# SparkFun_NanoBeacon_Lite_Board_-_IN100.net
KiCad netlist of a schematic drawn in EAGLE
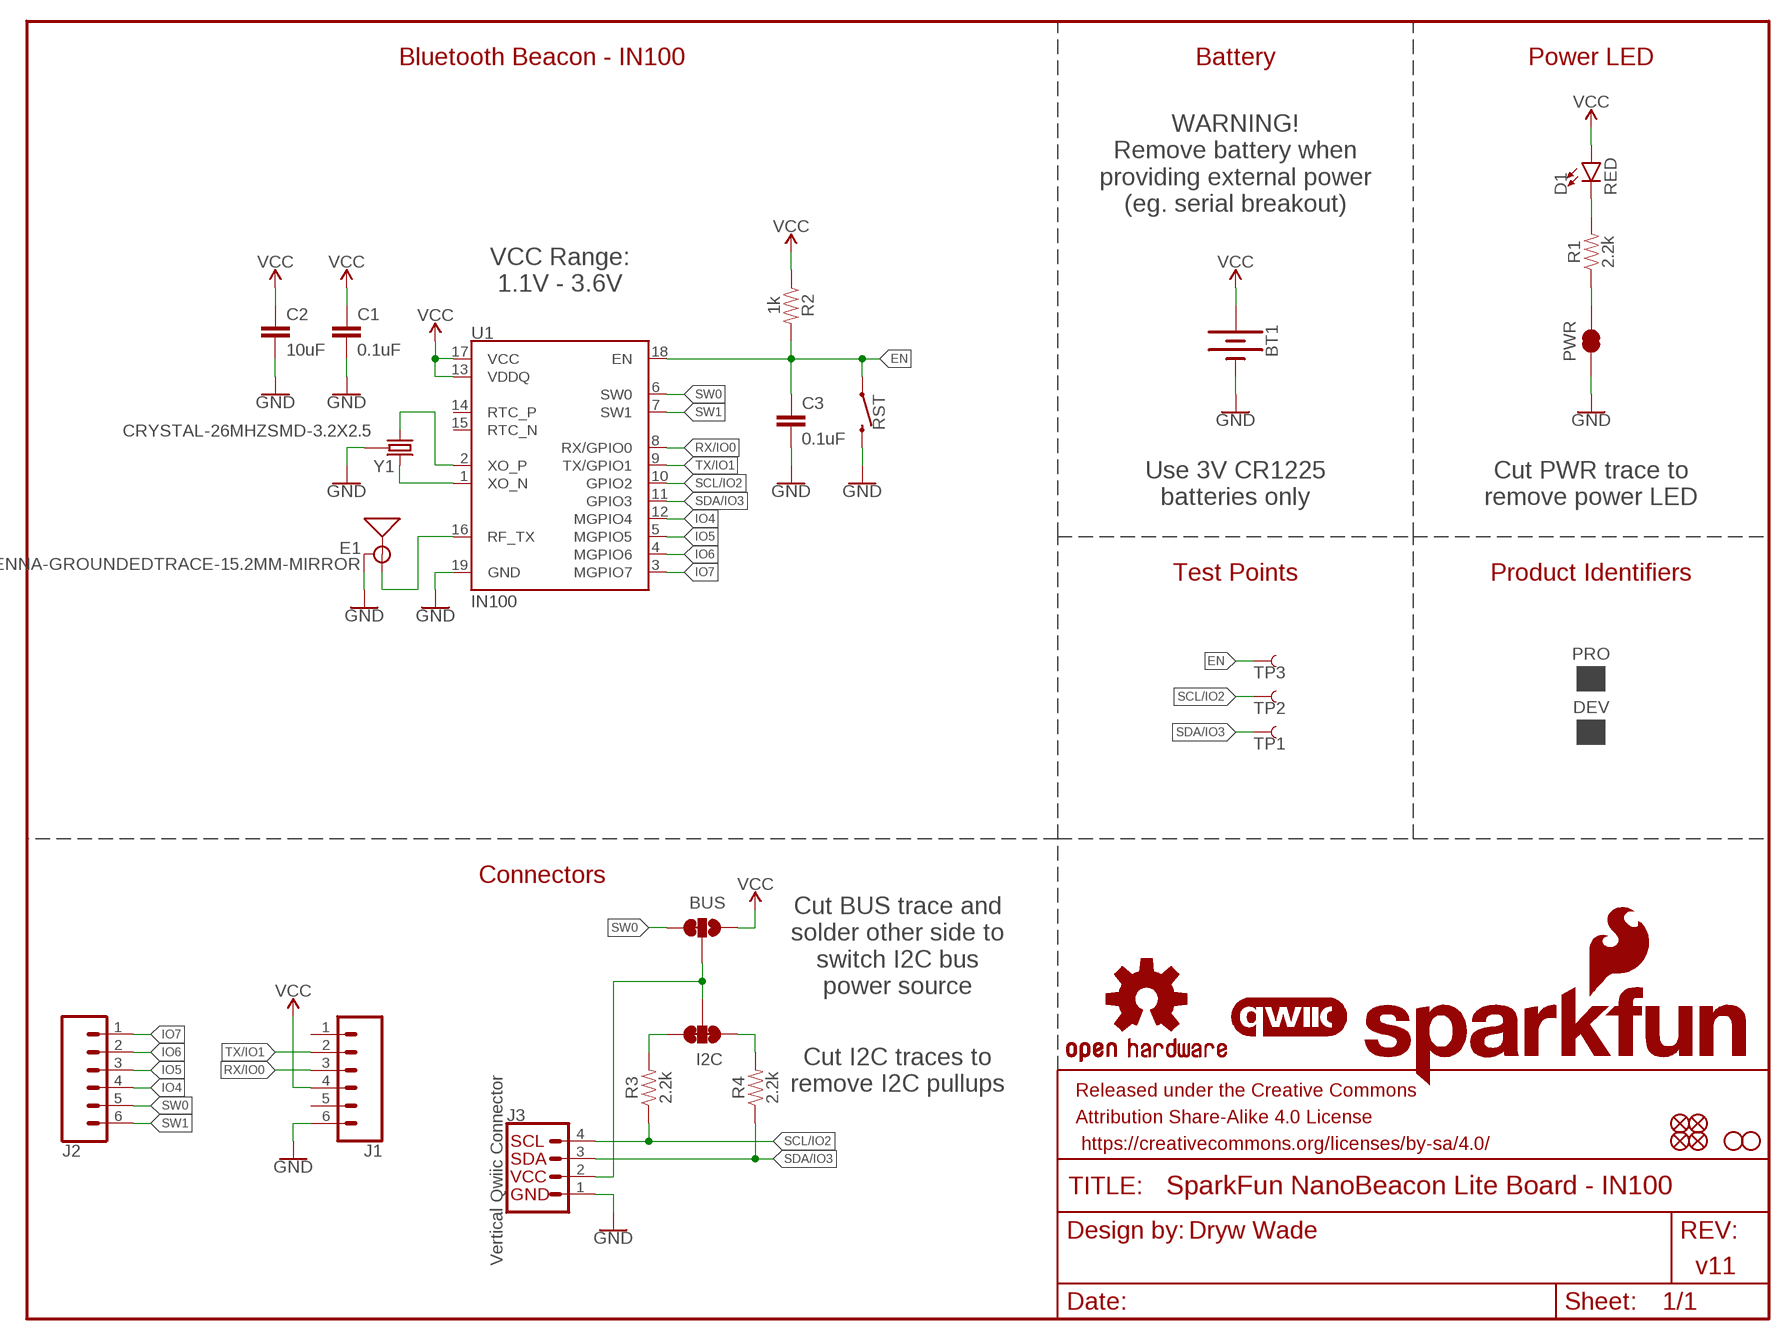
[diagram p0: schematic, sheet 1]

(export (version "E")
  (design (tool "Eeschema 10.0.6"))
  (components
    (comp (ref "BT1")
      (value "BATTERY-12MM_SMD_BOTH_PWR_PADS")
      (footprint "eagle-import:BATTCON_12MM")
      (libsource (lib "eagle-import") (part "BATTERY-12MM_SMD_BOTH_PWR_PADS"))
    )
    (comp (ref "BUS")
      (value "JUMPER-SMT_3_1-NC_TRACE_SILK")
      (footprint "eagle-import:SMT-JUMPER_3_1-NC_TRACE_SILK")
      (libsource (lib "eagle-import") (part "JUMPER-SMT_3_1-NC_TRACE_SILK"))
    )
    (comp (ref "C1")
      (value "0.1uF")
      (footprint "eagle-import:0402-TIGHT")
      (libsource (lib "eagle-import") (part "0.1UF-0402T-6.3V-10%-X7R"))
    )
    (comp (ref "C2")
      (value "10uF")
      (footprint "eagle-import:0402-TIGHT")
      (libsource (lib "eagle-import") (part "10UF-0402T-6.3V-20%"))
    )
    (comp (ref "C3")
      (value "0.1uF")
      (footprint "eagle-import:0402-TIGHT")
      (libsource (lib "eagle-import") (part "0.1UF-0402T-6.3V-10%-X7R"))
    )
    (comp (ref "D1")
      (value "RED")
      (footprint "eagle-import:LED-0402")
      (libsource (lib "eagle-import") (part "LED-RED_0402"))
    )
    (comp (ref "DEV")
      (value "PROD_ID_PASTE_SILK")
      (footprint "eagle-import:PRODUCT_IDENT_PASTE_SILK")
      (libsource (lib "eagle-import") (part "PROD_ID_PASTE_SILK"))
    )
    (comp (ref "E1")
      (value "ANTENNA-GROUNDEDTRACE-15.2MM-MIRROR")
      (footprint "eagle-import:TRACE_ANTENNA_2.4GHZ_15.2MM_MIRROR")
      (libsource (lib "eagle-import") (part "ANTENNA-GROUNDEDTRACE-15.2MM-MIRROR"))
    )
    (comp (ref "FD1")
      (value "FIDUCIAL1X2")
      (footprint "eagle-import:FIDUCIAL-1X2")
      (libsource (lib "eagle-import") (part "FIDUCIAL1X2"))
    )
    (comp (ref "FD2")
      (value "FIDUCIAL1X2")
      (footprint "eagle-import:FIDUCIAL-1X2")
      (libsource (lib "eagle-import") (part "FIDUCIAL1X2"))
    )
    (comp (ref "FD3")
      (value "FIDUCIAL1X2")
      (footprint "eagle-import:FIDUCIAL-1X2")
      (libsource (lib "eagle-import") (part "FIDUCIAL1X2"))
    )
    (comp (ref "FD4")
      (value "FIDUCIAL1X2")
      (footprint "eagle-import:FIDUCIAL-1X2")
      (libsource (lib "eagle-import") (part "FIDUCIAL1X2"))
    )
    (comp (ref "FRAME1")
      (value "FRAME-LETTER")
      (footprint "eagle-import:CREATIVE_COMMONS")
      (libsource (lib "eagle-import") (part "FRAME-LETTER"))
    )
    (comp (ref "H1")
      (value "STAND-OFF")
      (footprint "eagle-import:STAND-OFF")
      (libsource (lib "eagle-import") (part "STAND-OFF"))
    )
    (comp (ref "H2")
      (value "STAND-OFF")
      (footprint "eagle-import:STAND-OFF")
      (libsource (lib "eagle-import") (part "STAND-OFF"))
    )
    (comp (ref "I2C")
      (value "JUMPER-SMT_3_2-NC_TRACE_SILK")
      (footprint "eagle-import:SMT-JUMPER_3_2-NC_TRACE_SILK")
      (libsource (lib "eagle-import") (part "JUMPER-SMT_3_2-NC_TRACE_SILK"))
    )
    (comp (ref "J1")
      (value "CONN_06NO_SILK_NO_POP")
      (footprint "eagle-import:1X06_NO_SILK")
      (libsource (lib "eagle-import") (part "CONN_06NO_SILK_NO_POP"))
    )
    (comp (ref "J2")
      (value "CONN_06NO_SILK_NO_POP")
      (footprint "eagle-import:1X06_NO_SILK")
      (libsource (lib "eagle-import") (part "CONN_06NO_SILK_NO_POP"))
    )
    (comp (ref "J3")
      (value "Vertical Qwiic Connector")
      (footprint "eagle-import:JST04_1MM_VERT")
      (libsource (lib "eagle-import") (part "QWIIC_CONNECTOR"))
    )
    (comp (ref "LOGO1")
      (value "OSHW-LOGOS")
      (footprint "eagle-import:OSHW-LOGO-S")
      (libsource (lib "eagle-import") (part "OSHW-LOGOS"))
    )
    (comp (ref "LOGO2")
      (value "SFE_LOGO_NAME_FLAME.1_INCH")
      (footprint "eagle-import:SFE_LOGO_NAME_FLAME_.1")
      (libsource (lib "eagle-import") (part "SFE_LOGO_NAME_FLAME.1_INCH"))
    )
    (comp (ref "LOGO3")
      (value "QWIIC_LOGO_5MM")
      (footprint "eagle-import:QWIIC_5MM")
      (libsource (lib "eagle-import") (part "QWIIC_LOGO_5MM"))
    )
    (comp (ref "PRO")
      (value "PROD_ID_PASTE_SILK")
      (footprint "eagle-import:PRODUCT_IDENT_PASTE_SILK")
      (libsource (lib "eagle-import") (part "PROD_ID_PASTE_SILK"))
    )
    (comp (ref "PWR")
      (value "JUMPER-SMT_2_NC_TRACE_SILK")
      (footprint "eagle-import:SMT-JUMPER_2_NC_TRACE_SILK")
      (libsource (lib "eagle-import") (part "JUMPER-SMT_2_NC_TRACE_SILK"))
    )
    (comp (ref "R1")
      (value "2.2k")
      (footprint "eagle-import:0402-TIGHT")
      (libsource (lib "eagle-import") (part "2.2KOHM-0402T-1/16W-1%"))
    )
    (comp (ref "R2")
      (value "1k")
      (footprint "eagle-import:0402-TIGHT")
      (libsource (lib "eagle-import") (part "1KOHM-0402T-1/16W-1%"))
    )
    (comp (ref "R3")
      (value "2.2k")
      (footprint "eagle-import:0402-TIGHT")
      (libsource (lib "eagle-import") (part "2.2KOHM-0402T-1/16W-1%"))
    )
    (comp (ref "R4")
      (value "2.2k")
      (footprint "eagle-import:0402-TIGHT")
      (libsource (lib "eagle-import") (part "2.2KOHM-0402T-1/16W-1%"))
    )
    (comp (ref "RST")
      (value "MOMENTARY-SWITCH-SPST-SMD-4.6X2.8MM")
      (footprint "eagle-import:TACTILE_SWITCH_SMD_4.6X2.8MM")
      (libsource (lib "eagle-import") (part "MOMENTARY-SWITCH-SPST-SMD-4.6X2.8MM"))
    )
    (comp (ref "TP1")
      (value "TEST-POINT3")
      (footprint "eagle-import:PAD.03X.03")
      (libsource (lib "eagle-import") (part "TEST-POINT3"))
    )
    (comp (ref "TP2")
      (value "TEST-POINT3")
      (footprint "eagle-import:PAD.03X.03")
      (libsource (lib "eagle-import") (part "TEST-POINT3"))
    )
    (comp (ref "TP3")
      (value "TEST-POINT3")
      (footprint "eagle-import:PAD.03X.03")
      (libsource (lib "eagle-import") (part "TEST-POINT3"))
    )
    (comp (ref "U1")
      (value "IN100")
      (footprint "eagle-import:IN100")
      (libsource (lib "eagle-import") (part "IN100"))
    )
    (comp (ref "Y1")
      (value "CRYSTAL-26MHZSMD-3.2X2.5")
      (footprint "eagle-import:CRYSTAL-SMD-3.2X2.5MM")
      (libsource (lib "eagle-import") (part "CRYSTAL-26MHZSMD-3.2X2.5"))
    )
  )
  (nets
    (net (code "1") (name "EN") (class "Default")
      (node (ref "C3") (pin "1") (pinfunction "1_1") (pintype "passive"))
      (node (ref "R2") (pin "2") (pinfunction "2_2") (pintype "passive"))
      (node (ref "RST") (pin "1") (pinfunction "1_1") (pintype "passive"))
      (node (ref "RST") (pin "2") (pinfunction "1_2") (pintype "passive"))
      (node (ref "TP3") (pin "1") (pinfunction "1_1") (pintype "bidirectional"))
      (node (ref "U1") (pin "18") (pinfunction "EN_18") (pintype "input"))
    )
    (net (code "2") (name "GND") (class "Default")
      (node (ref "BT1") (pin "GND") (pinfunction "-_GND") (pintype "power_in"))
      (node (ref "C1") (pin "2") (pinfunction "2_2") (pintype "passive"))
      (node (ref "C2") (pin "2") (pinfunction "2_2") (pintype "passive"))
      (node (ref "C3") (pin "2") (pinfunction "2_2") (pintype "passive"))
      (node (ref "E1") (pin "GND") (pinfunction "GND_GND") (pintype "bidirectional"))
      (node (ref "J1") (pin "6") (pinfunction "6_6") (pintype "passive"))
      (node (ref "J3") (pin "1") (pinfunction "1_1") (pintype "power_in"))
      (node (ref "PWR") (pin "1") (pinfunction "1_1") (pintype "passive"))
      (node (ref "RST") (pin "3") (pinfunction "2_3") (pintype "passive"))
      (node (ref "RST") (pin "4") (pinfunction "2_4") (pintype "passive"))
      (node (ref "U1") (pin "19") (pinfunction "GND_19") (pintype "power_in"))
      (node (ref "Y1") (pin "2") (pinfunction "GND_2") (pintype "power_in"))
      (node (ref "Y1") (pin "4") (pinfunction "GND_4") (pintype "power_in"))
    )
    (net (code "3") (name "IO4") (class "Default")
      (node (ref "J2") (pin "4") (pinfunction "4_4") (pintype "passive"))
      (node (ref "U1") (pin "12") (pinfunction "MGPIO4_12") (pintype "bidirectional"))
    )
    (net (code "4") (name "IO5") (class "Default")
      (node (ref "J2") (pin "3") (pinfunction "3_3") (pintype "passive"))
      (node (ref "U1") (pin "5") (pinfunction "MGPIO5_5") (pintype "bidirectional"))
    )
    (net (code "5") (name "IO6") (class "Default")
      (node (ref "J2") (pin "2") (pinfunction "2_2") (pintype "passive"))
      (node (ref "U1") (pin "4") (pinfunction "MGPIO6_4") (pintype "bidirectional"))
    )
    (net (code "6") (name "IO7") (class "Default")
      (node (ref "J2") (pin "1") (pinfunction "1_1") (pintype "passive"))
      (node (ref "U1") (pin "3") (pinfunction "MGPIO7_3") (pintype "bidirectional"))
    )
    (net (code "7") (name "Net-(BUS-Pad2)") (class "Default")
      (node (ref "BUS") (pin "2") (pinfunction "2_2") (pintype "passive"))
      (node (ref "I2C") (pin "2") (pinfunction "2_2") (pintype "passive"))
      (node (ref "J3") (pin "2") (pinfunction "2_2") (pintype "power_in"))
    )
    (net (code "8") (name "Net-(D1-PadC)") (class "Default")
      (node (ref "D1") (pin "C") (pinfunction "C_C") (pintype "passive"))
      (node (ref "R1") (pin "2") (pinfunction "2_2") (pintype "passive"))
    )
    (net (code "9") (name "Net-(E1-SIGNAL)") (class "Default")
      (node (ref "E1") (pin "ANT") (pinfunction "SIGNAL_ANT") (pintype "bidirectional"))
      (node (ref "U1") (pin "16") (pinfunction "RF_TX_16") (pintype "bidirectional"))
    )
    (net (code "10") (name "Net-(I2C-Pad1)") (class "Default")
      (node (ref "I2C") (pin "1") (pinfunction "1_1") (pintype "passive"))
      (node (ref "R4") (pin "2") (pinfunction "2_2") (pintype "passive"))
    )
    (net (code "11") (name "Net-(I2C-Pad3)") (class "Default")
      (node (ref "I2C") (pin "3") (pinfunction "3_3") (pintype "passive"))
      (node (ref "R3") (pin "2") (pinfunction "2_2") (pintype "passive"))
    )
    (net (code "12") (name "Net-(PWR-Pad2)") (class "Default")
      (node (ref "PWR") (pin "2") (pinfunction "2_2") (pintype "passive"))
      (node (ref "R1") (pin "1") (pinfunction "1_1") (pintype "passive"))
    )
    (net (code "13") (name "Net-(U1-XO_N)") (class "Default")
      (node (ref "U1") (pin "1") (pinfunction "XO_N_1") (pintype "bidirectional"))
      (node (ref "Y1") (pin "3") (pinfunction "2_3") (pintype "passive"))
    )
    (net (code "14") (name "Net-(U1-XO_P)") (class "Default")
      (node (ref "U1") (pin "2") (pinfunction "XO_P_2") (pintype "bidirectional"))
      (node (ref "Y1") (pin "1") (pinfunction "1_1") (pintype "passive"))
    )
    (net (code "15") (name "RX{slash}IO0") (class "Default")
      (node (ref "J1") (pin "3") (pinfunction "3_3") (pintype "passive"))
      (node (ref "U1") (pin "8") (pinfunction "RX/GPIO0_8") (pintype "bidirectional"))
    )
    (net (code "16") (name "SCL{slash}IO2") (class "Default")
      (node (ref "J3") (pin "4") (pinfunction "4_4") (pintype "passive"))
      (node (ref "R3") (pin "1") (pinfunction "1_1") (pintype "passive"))
      (node (ref "TP2") (pin "1") (pinfunction "1_1") (pintype "bidirectional"))
      (node (ref "U1") (pin "10") (pinfunction "GPIO2_10") (pintype "bidirectional"))
    )
    (net (code "17") (name "SDA{slash}IO3") (class "Default")
      (node (ref "J3") (pin "3") (pinfunction "3_3") (pintype "passive"))
      (node (ref "R4") (pin "1") (pinfunction "1_1") (pintype "passive"))
      (node (ref "TP1") (pin "1") (pinfunction "1_1") (pintype "bidirectional"))
      (node (ref "U1") (pin "11") (pinfunction "GPIO3_11") (pintype "bidirectional"))
    )
    (net (code "18") (name "SW0") (class "Default")
      (node (ref "BUS") (pin "3") (pinfunction "3_3") (pintype "passive"))
      (node (ref "J2") (pin "5") (pinfunction "5_5") (pintype "passive"))
      (node (ref "U1") (pin "6") (pinfunction "SW0_6") (pintype "output"))
    )
    (net (code "19") (name "SW1") (class "Default")
      (node (ref "J2") (pin "6") (pinfunction "6_6") (pintype "passive"))
      (node (ref "U1") (pin "7") (pinfunction "SW1_7") (pintype "output"))
    )
    (net (code "20") (name "TX{slash}IO1") (class "Default")
      (node (ref "J1") (pin "2") (pinfunction "2_2") (pintype "passive"))
      (node (ref "U1") (pin "9") (pinfunction "TX/GPIO1_9") (pintype "bidirectional"))
    )
    (net (code "21") (name "VCC") (class "Default")
      (node (ref "BT1") (pin "PWR@1") (pinfunction "+_PWR@1") (pintype "power_in"))
      (node (ref "BT1") (pin "PWR@2") (pinfunction "+_PWR@2") (pintype "power_in"))
      (node (ref "BUS") (pin "1") (pinfunction "1_1") (pintype "passive"))
      (node (ref "C1") (pin "1") (pinfunction "1_1") (pintype "passive"))
      (node (ref "C2") (pin "1") (pinfunction "1_1") (pintype "passive"))
      (node (ref "D1") (pin "A") (pinfunction "A_A") (pintype "passive"))
      (node (ref "J1") (pin "4") (pinfunction "4_4") (pintype "passive"))
      (node (ref "R2") (pin "1") (pinfunction "1_1") (pintype "passive"))
      (node (ref "U1") (pin "13") (pinfunction "VDDQ_13") (pintype "power_in"))
      (node (ref "U1") (pin "17") (pinfunction "VCC_17") (pintype "power_in"))
    )
    (net (code "22") (name "unconnected-(J1-Pad1)") (class "Default")
      (node (ref "J1") (pin "1") (pinfunction "1_1") (pintype "passive"))
    )
    (net (code "23") (name "unconnected-(J1-Pad5)") (class "Default")
      (node (ref "J1") (pin "5") (pinfunction "5_5") (pintype "passive"))
    )
    (net (code "24") (name "unconnected-(U1-RTC_N-Pad15)") (class "Default")
      (node (ref "U1") (pin "15") (pinfunction "RTC_N_15") (pintype "bidirectional"))
    )
    (net (code "25") (name "unconnected-(U1-RTC_P-Pad14)") (class "Default")
      (node (ref "U1") (pin "14") (pinfunction "RTC_P_14") (pintype "bidirectional"))
    )
  )
)
